# ESM-4G-V1_1.net
KiCad netlist of a schematic drawn in Altium Designer
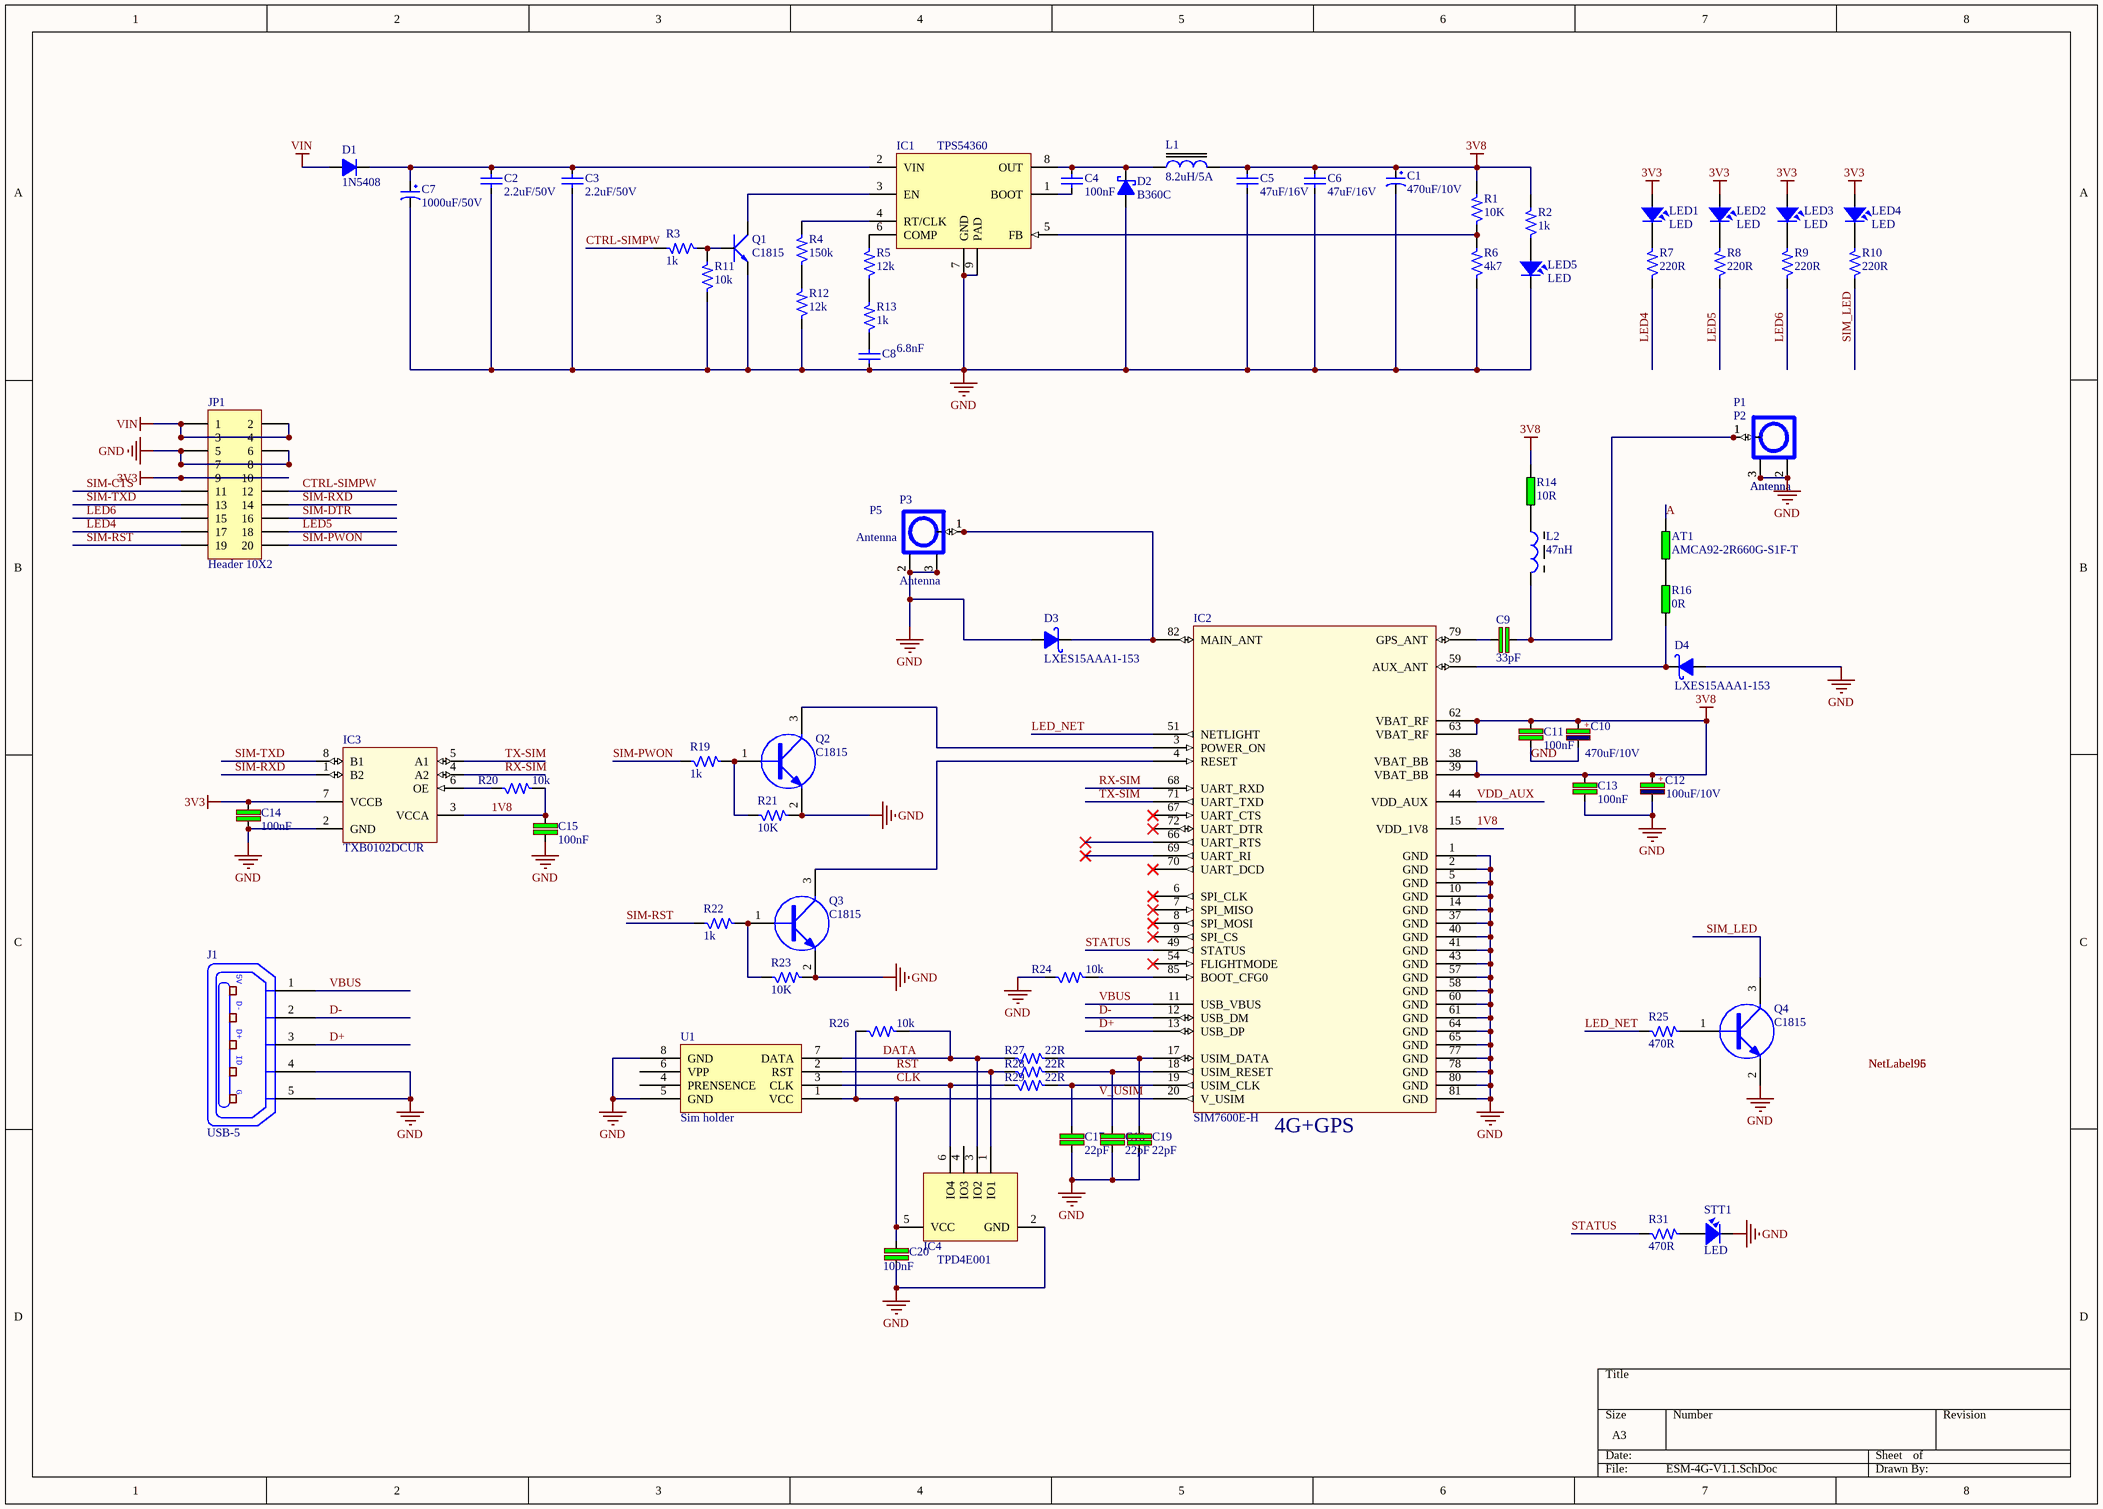
[diagram p0: ESM-4G-V1.1.SchDoc]

(export (version "E")
  (design (tool "Eeschema 10.0.6"))
  (components
    (comp (ref "AT1")
      (value "AMCA92-2R660G-S1F-T")
      (footprint "Antena-Chip - LTE")
      (description "Resistor 1/4W")
      (libsource (lib "heromap") (part "RES"))
    )
    (comp (ref "C1")
      (value "470uF/10V")
      (footprint "Anh_Trung:EEFSDE")
      (libsource (lib "Keolac") (part "CP"))
    )
    (comp (ref "C2")
      (value "2.2uF/50V")
      (footprint "Anh_Trung:C-1210")
      (description "part C3225X7R2A225K230AB")
      (libsource (lib "Keolac") (part "CN"))
    )
    (comp (ref "C3")
      (value "2.2uF/50V")
      (footprint "Anh_Trung:C-1210")
      (description "part C3225X7R2A225K230AB")
      (libsource (lib "Keolac") (part "CN"))
    )
    (comp (ref "C4") (value "100nF") (footprint "C-0805") (libsource (lib "Keolac") (part "CN")))
    (comp (ref "C5") (value "47uF/16V") (footprint "C-1210") (libsource (lib "Keolac") (part "CN")))
    (comp (ref "C6") (value "47uF/16V") (footprint "C-1210") (libsource (lib "Keolac") (part "CN")))
    (comp (ref "C7") (value "1000uF/50V") (footprint "CP5-10x16N") (libsource (lib "Keolac") (part "CP")))
    (comp (ref "C8") (value "6.8nF") (footprint "C-0805") (libsource (lib "Keolac") (part "CN")))
    (comp (ref "C9")
      (value "33pF")
      (footprint "C-0805")
      (description "Cap SMD")
      (libsource (lib "") (part "C_1"))
    )
    (comp (ref "C10")
      (value "470uF/10V")
      (footprint "EEFSDE")
      (description "Cap 1000uF/16V - 220uF/50V")
      (libsource (lib "heromap") (part "CP4"))
    )
    (comp (ref "C11")
      (value "100nF")
      (footprint "C-0805")
      (description "Cap SMD")
      (libsource (lib "heromap") (part "C"))
    )
    (comp (ref "C12")
      (value "100uF/10V")
      (footprint "EEFSDE")
      (description "Cap 1000uF/16V - 220uF/50V")
      (libsource (lib "heromap") (part "CP4"))
    )
    (comp (ref "C13")
      (value "100nF")
      (footprint "C-0805")
      (description "Cap SMD")
      (libsource (lib "heromap") (part "C"))
    )
    (comp (ref "C14")
      (value "100nF")
      (footprint "C-0805")
      (description "Cap SMD")
      (libsource (lib "heromap") (part "C"))
    )
    (comp (ref "C15")
      (value "100nF")
      (footprint "C-0805")
      (description "Cap SMD")
      (libsource (lib "heromap") (part "C"))
    )
    (comp (ref "C17")
      (value "22pF")
      (footprint "C-0805")
      (description "Cap SMD")
      (libsource (lib "heromap") (part "C"))
    )
    (comp (ref "C18")
      (value "22pF")
      (footprint "C-0805")
      (description "Cap SMD")
      (libsource (lib "heromap") (part "C"))
    )
    (comp (ref "C19")
      (value "22pF")
      (footprint "C-0805")
      (description "Cap SMD")
      (libsource (lib "heromap") (part "C"))
    )
    (comp (ref "C20")
      (value "100nF")
      (footprint "C-0805")
      (description "Cap SMD")
      (libsource (lib "heromap") (part "C"))
    )
    (comp (ref "D1")
      (value "1N5408")
      (footprint "Duy_Hai:SMB")
      (description "Diode S3M 3A 1000V")
      (libsource (lib "Keolac") (part "Diode"))
    )
    (comp (ref "D2")
      (value "B360C")
      (footprint "DUNV:SMB")
      (description "part: B560C-13-F")
      (libsource (lib "Keolac") (part "Diode scotky"))
    )
    (comp (ref "D3")
      (value "LXES15AAA1-153")
      (footprint "R-0402")
      (libsource (lib "Anh_Trung") (part "1N5822"))
    )
    (comp (ref "D4")
      (value "LXES15AAA1-153")
      (footprint "R-0402")
      (libsource (lib "Anh_Trung") (part "1N5822"))
    )
    (comp (ref "IC1")
      (value "TPS54360")
      (footprint "Anh_Trung:SOIC-8 - PW")
      (description "TPS54360 60 V Input, 3.5 A, Step Down DC-DC Converter with Eco-mode™")
      (libsource (lib "Keolac") (part "TPS54360"))
    )
    (comp (ref "IC2")
      (value "SIM7600E-H")
      (footprint "SIM7600")
      (description "SIM7600E-H GSM/LTE CAT4/GPS")
      (libsource (lib "Anh_Trung") (part "SIM7600E-H"))
    )
    (comp (ref "IC3")
      (value "TXB0102DCUR")
      (footprint "Duy_Hai:US8")
      (description "2-BIT BIDIRECTIONAL VOLTAGE-LEVEL TRANSLATOR")
      (libsource (lib "Anh_Trung") (part "TXB0102DCUR"))
    )
    (comp (ref "IC4")
      (value "TPD4E001")
      (footprint "SOT23-6 - 2")
      (libsource (lib "heromap") (part "TPD4E001"))
    )
    (comp (ref "J1")
      (value "USB-5")
      (footprint "USB-M2")
      (fields
        (field (name "MANUFACTURER") "FCI")
        (field (name "MANUFACTURER PART NUMBER") "10118193-0001LF")
        (field (name ".CREATOR") "MM")
        (field (name ".CHECKED PCB") "RF")
        (field (name ".CHECKED SCH") "MM")
      )
      (libsource (lib "Duy_Hai") (part "USB-5"))
    )
    (comp (ref "JP1")
      (value "Header 10X2")
      (footprint "Duy_Hai:JP10x2-FMD-2.54")
      (description "Header, 10-Pin, Dual row")
      (fields (field (name "PUBLISHER") "Altium Limited"))
      (libsource (lib "heromap") (part "Header 10X2"))
    )
    (comp (ref "L1")
      (value "8.2uH/5A")
      (footprint "Keolac:L-L-12x12")
      (description "part: 7447797820")
      (libsource (lib "Keolac") (part "L1"))
    )
    (comp (ref "L2")
      (value "47nH")
      (footprint "L-0805")
      (description "Ferrite Beads Rated current > 1A")
      (libsource (lib "heromap") (part "Inductor Ferit"))
    )
    (comp (ref "LED1") (value "LED") (footprint "Keolac:LED-5-N") (libsource (lib "Keolac") (part "LED")))
    (comp (ref "LED2") (value "LED") (footprint "Keolac:LED-5-N") (libsource (lib "Keolac") (part "LED")))
    (comp (ref "LED3") (value "LED") (footprint "Keolac:LED-5-N") (libsource (lib "Keolac") (part "LED")))
    (comp (ref "LED4") (value "LED") (footprint "Keolac:LED-5-N") (libsource (lib "Keolac") (part "LED")))
    (comp (ref "LED5") (value "LED") (footprint "Anh_Trung:LED-0805") (libsource (lib "Keolac") (part "LED")))
    (comp (ref "P1")
      (value "Antenna")
      (footprint "Duy_Hai:IPXS_1")
      (description "Antenna GSM GPS")
      (libsource (lib "heromap") (part "IPXSx66"))
    )
    (comp (ref "P2")
      (value "Antenna")
      (footprint "IPXS")
      (description "Antenna GSM GPS")
      (libsource (lib "heromap") (part "IPXSx66"))
    )
    (comp (ref "P3")
      (value "Antenna")
      (footprint "Duy_Hai:IPXS_1")
      (description "Antenna GSM GPS")
      (libsource (lib "") (part "IPXSx66_1"))
    )
    (comp (ref "P5")
      (value "Antenna")
      (footprint "IPXS")
      (description "Antenna GSM GPS")
      (libsource (lib "") (part "IPXSx66_1"))
    )
    (comp (ref "Q1")
      (value "C1815")
      (footprint "Keolac:SOT23-3 Tran")
      (libsource (lib "Keolac") (part "C1815"))
    )
    (comp (ref "Q2")
      (value "C1815")
      (footprint "SOT23")
      (description "Transistor C1815, SOT23")
      (fields (field (name "NAME") "C1815"))
      (libsource (lib "Library") (part "NPN"))
    )
    (comp (ref "Q3")
      (value "C1815")
      (footprint "SOT23")
      (description "Transistor C1815, SOT23")
      (fields (field (name "NAME") "C1815"))
      (libsource (lib "Library") (part "NPN"))
    )
    (comp (ref "Q4")
      (value "C1815(MMBT4401)")
      (footprint "SOT23")
      (description "Transistor C1815, SOT23")
      (fields (field (name "NAME") "C1815"))
      (libsource (lib "Library") (part "NPN"))
    )
    (comp (ref "R1")
      (value "10K")
      (footprint "Anh_Trung:R-0805")
      (description "Resistor 1/4W")
      (libsource (lib "Keolac") (part "R"))
    )
    (comp (ref "R2")
      (value "1k")
      (footprint "Anh_Trung:R-0805")
      (description "Resistor 1/4W")
      (libsource (lib "Keolac") (part "R"))
    )
    (comp (ref "R3")
      (value "1k")
      (footprint "Anh_Trung:R-0805")
      (description "Resistor 1/4W")
      (libsource (lib "Keolac") (part "R"))
    )
    (comp (ref "R4")
      (value "150k")
      (footprint "Anh_Trung:R-0805")
      (description "Resistor 1/4W")
      (libsource (lib "Keolac") (part "R"))
    )
    (comp (ref "R5")
      (value "12k")
      (footprint "R-0805")
      (description "Resistor 1/4W")
      (libsource (lib "Keolac") (part "R"))
    )
    (comp (ref "R6")
      (value "4k7")
      (footprint "Anh_Trung:R-0805")
      (description "Resistor 1/4W")
      (libsource (lib "Keolac") (part "R"))
    )
    (comp (ref "R7")
      (value "220R")
      (footprint "Anh_Trung:R-0805")
      (description "Resistor 1/4W")
      (libsource (lib "Keolac") (part "R"))
    )
    (comp (ref "R8")
      (value "220R")
      (footprint "Anh_Trung:R-0805")
      (description "Resistor 1/4W")
      (libsource (lib "Keolac") (part "R"))
    )
    (comp (ref "R9")
      (value "220R")
      (footprint "Anh_Trung:R-0805")
      (description "Resistor 1/4W")
      (libsource (lib "Keolac") (part "R"))
    )
    (comp (ref "R10")
      (value "220R")
      (footprint "Anh_Trung:R-0805")
      (description "Resistor 1/4W")
      (libsource (lib "Keolac") (part "R"))
    )
    (comp (ref "R11")
      (value "10k")
      (footprint "Anh_Trung:R-0805")
      (description "Resistor 1/4W")
      (libsource (lib "Keolac") (part "R"))
    )
    (comp (ref "R12")
      (value "12k")
      (footprint "Anh_Trung:R-0805")
      (description "Resistor 1/4W")
      (libsource (lib "Keolac") (part "R"))
    )
    (comp (ref "R13")
      (value "1k")
      (footprint "Anh_Trung:R-0805")
      (description "Resistor 1/4W")
      (libsource (lib "Keolac") (part "R"))
    )
    (comp (ref "R14")
      (value "10R")
      (footprint "R-0805")
      (description "Resistor 1/4W")
      (libsource (lib "heromap") (part "RES"))
    )
    (comp (ref "R16")
      (value "0R")
      (footprint "R-0805")
      (description "Resistor 1/4W")
      (libsource (lib "heromap") (part "RES"))
    )
    (comp (ref "R19")
      (value "1k")
      (footprint "R-0805")
      (description "Resistor 1/4W")
      (libsource (lib "Keolac") (part "R"))
    )
    (comp (ref "R20")
      (value "10k")
      (footprint "R-0805")
      (description "Resistor 1/4W")
      (libsource (lib "Keolac") (part "R"))
    )
    (comp (ref "R21")
      (value "10K")
      (footprint "R-0805")
      (description "Resistor 1/4W")
      (libsource (lib "Keolac") (part "R"))
    )
    (comp (ref "R22")
      (value "1k")
      (footprint "R-0805")
      (description "Resistor 1/4W")
      (libsource (lib "Keolac") (part "R"))
    )
    (comp (ref "R23")
      (value "10K")
      (footprint "R-0805")
      (description "Resistor 1/4W")
      (libsource (lib "Keolac") (part "R"))
    )
    (comp (ref "R24")
      (value "10k")
      (footprint "R-0805")
      (description "Resistor 1/4W")
      (libsource (lib "Keolac") (part "R"))
    )
    (comp (ref "R25")
      (value "470R")
      (footprint "R-0805")
      (description "Resistor 1/4W")
      (libsource (lib "heromap") (part "R"))
    )
    (comp (ref "R26")
      (value "10k")
      (footprint "R-0805")
      (description "Resistor 1/4W")
      (libsource (lib "Keolac") (part "R"))
    )
    (comp (ref "R27")
      (value "22R")
      (footprint "R-0805")
      (description "Resistor 1/4W")
      (libsource (lib "Keolac") (part "R"))
    )
    (comp (ref "R28")
      (value "22R")
      (footprint "R-0805")
      (description "Resistor 1/4W")
      (libsource (lib "Keolac") (part "R"))
    )
    (comp (ref "R29")
      (value "22R")
      (footprint "R-0805")
      (description "Resistor 1/4W")
      (libsource (lib "Keolac") (part "R"))
    )
    (comp (ref "R31")
      (value "470R")
      (footprint "R-0805")
      (description "Resistor 1/4W")
      (libsource (lib "heromap") (part "R"))
    )
    (comp (ref "STT1")
      (value "LED")
      (footprint "LED-SMD-0805")
      (description "LED Single colour Green and Red")
      (libsource (lib "heromap") (part "LED"))
    )
    (comp (ref "U1")
      (value "Sim holder")
      (footprint "Duy_Hai:SIM_HOLDER")
      (libsource (lib "Sim holder") (part "Component_1"))
    )
  )
  (nets
    (net (code "1") (name "/1V8") (class "Default")
      (node (ref "C15") (pin "1") (pinfunction "1_1") (pintype "passive"))
      (node (ref "IC2") (pin "15") (pinfunction "VDD_1V8_15") (pintype "passive"))
      (node (ref "IC3") (pin "3") (pinfunction "VCCA_3") (pintype "power_in"))
      (node (ref "R20") (pin "2") (pinfunction "2_2") (pintype "passive"))
    )
    (net (code "2") (name "/A") (class "Default")
      (node (ref "AT1") (pin "2") (pinfunction "2_2") (pintype "passive"))
    )
    (net (code "3") (name "/CLK") (class "Default")
      (node (ref "IC4") (pin "6") (pinfunction "IO4_6") (pintype "passive"))
      (node (ref "R29") (pin "1") (pinfunction "1_1") (pintype "passive"))
      (node (ref "U1") (pin "3") (pinfunction "CLK_3") (pintype "passive"))
    )
    (net (code "4") (name "/CTRL-SIMPW") (class "Default")
      (node (ref "JP1") (pin "12") (pinfunction "12_12") (pintype "passive"))
      (node (ref "R3") (pin "2") (pinfunction "2_2") (pintype "passive"))
    )
    (net (code "5") (name "/D+") (class "Default")
      (node (ref "IC2") (pin "13") (pinfunction "USB_DP_13") (pintype "bidirectional"))
      (node (ref "J1") (pin "3") (pinfunction "P3_3") (pintype "passive"))
    )
    (net (code "6") (name "/D-") (class "Default")
      (node (ref "IC2") (pin "12") (pinfunction "USB_DM_12") (pintype "bidirectional"))
      (node (ref "J1") (pin "2") (pinfunction "P2_2") (pintype "passive"))
    )
    (net (code "7") (name "/DATA") (class "Default")
      (node (ref "IC4") (pin "3") (pinfunction "IO2_3") (pintype "passive"))
      (node (ref "R26") (pin "2") (pinfunction "2_2") (pintype "passive"))
      (node (ref "R27") (pin "1") (pinfunction "1_1") (pintype "passive"))
      (node (ref "U1") (pin "7") (pinfunction "DATA_7") (pintype "passive"))
    )
    (net (code "8") (name "/LED4") (class "Default")
      (node (ref "JP1") (pin "17") (pinfunction "17_17") (pintype "passive"))
      (node (ref "R7") (pin "1") (pinfunction "1_1") (pintype "passive"))
    )
    (net (code "9") (name "/LED5") (class "Default")
      (node (ref "JP1") (pin "18") (pinfunction "18_18") (pintype "passive"))
      (node (ref "R8") (pin "1") (pinfunction "1_1") (pintype "passive"))
    )
    (net (code "10") (name "/LED6") (class "Default")
      (node (ref "JP1") (pin "15") (pinfunction "15_15") (pintype "passive"))
      (node (ref "R9") (pin "1") (pinfunction "1_1") (pintype "passive"))
    )
    (net (code "11") (name "/LED_NET") (class "Default")
      (node (ref "IC2") (pin "51") (pinfunction "NETLIGHT_51") (pintype "output"))
      (node (ref "R25") (pin "1") (pinfunction "1_1") (pintype "passive"))
    )
    (net (code "13") (name "/RST") (class "Default")
      (node (ref "IC4") (pin "1") (pinfunction "IO1_1") (pintype "passive"))
      (node (ref "R28") (pin "1") (pinfunction "1_1") (pintype "passive"))
      (node (ref "U1") (pin "2") (pinfunction "RST_2") (pintype "passive"))
    )
    (net (code "14") (name "/RX-SIM") (class "Default")
      (node (ref "IC2") (pin "68") (pinfunction "UART_RXD_68") (pintype "input"))
      (node (ref "IC3") (pin "4") (pinfunction "A2_4") (pintype "bidirectional"))
    )
    (net (code "15") (name "/SIM-CTS") (class "Default")
      (node (ref "JP1") (pin "11") (pinfunction "11_11") (pintype "passive"))
    )
    (net (code "16") (name "/SIM-DTR") (class "Default")
      (node (ref "JP1") (pin "16") (pinfunction "16_16") (pintype "passive"))
    )
    (net (code "17") (name "/SIM-PWON") (class "Default")
      (node (ref "JP1") (pin "20") (pinfunction "20_20") (pintype "passive"))
      (node (ref "R19") (pin "1") (pinfunction "1_1") (pintype "passive"))
    )
    (net (code "18") (name "/SIM-RST") (class "Default")
      (node (ref "JP1") (pin "19") (pinfunction "19_19") (pintype "passive"))
      (node (ref "R22") (pin "1") (pinfunction "1_1") (pintype "passive"))
    )
    (net (code "19") (name "/SIM-RXD") (class "Default")
      (node (ref "IC3") (pin "1") (pinfunction "B2_1") (pintype "bidirectional"))
      (node (ref "JP1") (pin "14") (pinfunction "14_14") (pintype "passive"))
    )
    (net (code "20") (name "/SIM-TXD") (class "Default")
      (node (ref "IC3") (pin "8") (pinfunction "B1_8") (pintype "bidirectional"))
      (node (ref "JP1") (pin "13") (pinfunction "13_13") (pintype "passive"))
    )
    (net (code "21") (name "/SIM_LED") (class "Default")
      (node (ref "Q4") (pin "3") (pinfunction "C_3") (pintype "passive"))
      (node (ref "R10") (pin "1") (pinfunction "1_1") (pintype "passive"))
    )
    (net (code "22") (name "/STATUS") (class "Default")
      (node (ref "IC2") (pin "49") (pinfunction "STATUS_49") (pintype "output"))
      (node (ref "R31") (pin "1") (pinfunction "1_1") (pintype "passive"))
    )
    (net (code "23") (name "/TX-SIM") (class "Default")
      (node (ref "IC2") (pin "71") (pinfunction "UART_TXD_71") (pintype "output"))
      (node (ref "IC3") (pin "5") (pinfunction "A1_5") (pintype "bidirectional"))
    )
    (net (code "24") (name "/VBUS") (class "Default")
      (node (ref "IC2") (pin "11") (pinfunction "USB_VBUS_11") (pintype "passive"))
      (node (ref "J1") (pin "1") (pinfunction "P1_1") (pintype "passive"))
    )
    (net (code "25") (name "/VDD_AUX") (class "Default")
      (node (ref "IC2") (pin "44") (pinfunction "VDD_AUX_44") (pintype "passive"))
    )
    (net (code "26") (name "/V_USIM") (class "Default")
      (node (ref "C20") (pin "1") (pinfunction "1_1") (pintype "passive"))
      (node (ref "IC2") (pin "20") (pinfunction "V_USIM_20") (pintype "output"))
      (node (ref "IC4") (pin "5") (pinfunction "VCC_5") (pintype "passive"))
      (node (ref "R26") (pin "1") (pinfunction "1_1") (pintype "passive"))
      (node (ref "U1") (pin "1") (pinfunction "VCC_1") (pintype "passive"))
    )
    (net (code "27") (name "3V3") (class "Default")
      (node (ref "C14") (pin "1") (pinfunction "1_1") (pintype "passive"))
      (node (ref "IC3") (pin "7") (pinfunction "VCCB_7") (pintype "power_in"))
      (node (ref "JP1") (pin "10") (pinfunction "10_10") (pintype "passive"))
      (node (ref "JP1") (pin "9") (pinfunction "9_9") (pintype "passive"))
      (node (ref "LED1") (pin "1") (pinfunction "1_1") (pintype "passive"))
      (node (ref "LED2") (pin "1") (pinfunction "1_1") (pintype "passive"))
      (node (ref "LED3") (pin "1") (pinfunction "1_1") (pintype "passive"))
      (node (ref "LED4") (pin "1") (pinfunction "1_1") (pintype "passive"))
    )
    (net (code "28") (name "3V8") (class "Default")
      (node (ref "C1") (pin "1") (pinfunction "1_1") (pintype "passive"))
      (node (ref "C10") (pin "1") (pinfunction "1_1") (pintype "passive"))
      (node (ref "C11") (pin "1") (pinfunction "1_1") (pintype "passive"))
      (node (ref "C12") (pin "1") (pinfunction "1_1") (pintype "passive"))
      (node (ref "C13") (pin "1") (pinfunction "1_1") (pintype "passive"))
      (node (ref "C5") (pin "2") (pinfunction "2_2") (pintype "passive"))
      (node (ref "C6") (pin "2") (pinfunction "2_2") (pintype "passive"))
      (node (ref "IC2") (pin "38") (pinfunction "VBAT_BB_38") (pintype "passive"))
      (node (ref "IC2") (pin "39") (pinfunction "VBAT_BB_39") (pintype "passive"))
      (node (ref "IC2") (pin "62") (pinfunction "VBAT_RF_62") (pintype "passive"))
      (node (ref "IC2") (pin "63") (pinfunction "VBAT_RF_63") (pintype "passive"))
      (node (ref "L1") (pin "2") (pinfunction "2_2") (pintype "passive"))
      (node (ref "R1") (pin "2") (pinfunction "2_2") (pintype "passive"))
      (node (ref "R14") (pin "2") (pinfunction "2_2") (pintype "passive"))
      (node (ref "R2") (pin "2") (pinfunction "2_2") (pintype "passive"))
    )
    (net (code "29") (name "GND") (class "Default")
      (node (ref "C1") (pin "2") (pinfunction "2_2") (pintype "passive"))
      (node (ref "C10") (pin "2") (pinfunction "2_2") (pintype "passive"))
      (node (ref "C11") (pin "2") (pinfunction "2_2") (pintype "passive"))
      (node (ref "C12") (pin "2") (pinfunction "2_2") (pintype "passive"))
      (node (ref "C13") (pin "2") (pinfunction "2_2") (pintype "passive"))
      (node (ref "C14") (pin "2") (pinfunction "2_2") (pintype "passive"))
      (node (ref "C15") (pin "2") (pinfunction "2_2") (pintype "passive"))
      (node (ref "C17") (pin "2") (pinfunction "2_2") (pintype "passive"))
      (node (ref "C18") (pin "2") (pinfunction "2_2") (pintype "passive"))
      (node (ref "C19") (pin "2") (pinfunction "2_2") (pintype "passive"))
      (node (ref "C2") (pin "1") (pinfunction "1_1") (pintype "passive"))
      (node (ref "C20") (pin "2") (pinfunction "2_2") (pintype "passive"))
      (node (ref "C3") (pin "1") (pinfunction "1_1") (pintype "passive"))
      (node (ref "C5") (pin "1") (pinfunction "1_1") (pintype "passive"))
      (node (ref "C6") (pin "1") (pinfunction "1_1") (pintype "passive"))
      (node (ref "C7") (pin "2") (pinfunction "2_2") (pintype "passive"))
      (node (ref "C8") (pin "1") (pinfunction "1_1") (pintype "passive"))
      (node (ref "D2") (pin "1") (pinfunction "A_1") (pintype "passive"))
      (node (ref "D3") (pin "1") (pinfunction "A_1") (pintype "passive"))
      (node (ref "D4") (pin "1") (pinfunction "A_1") (pintype "passive"))
      (node (ref "IC1") (pin "7") (pinfunction "GND_7") (pintype "power_in"))
      (node (ref "IC1") (pin "9") (pinfunction "PAD_9") (pintype "power_in"))
      (node (ref "IC2") (pin "1") (pinfunction "GND_1") (pintype "passive"))
      (node (ref "IC2") (pin "10") (pinfunction "GND_10") (pintype "passive"))
      (node (ref "IC2") (pin "14") (pinfunction "GND_14") (pintype "passive"))
      (node (ref "IC2") (pin "2") (pinfunction "GND_2") (pintype "passive"))
      (node (ref "IC2") (pin "37") (pinfunction "GND_37") (pintype "passive"))
      (node (ref "IC2") (pin "40") (pinfunction "GND_40") (pintype "passive"))
      (node (ref "IC2") (pin "41") (pinfunction "GND_41") (pintype "passive"))
      (node (ref "IC2") (pin "43") (pinfunction "GND_43") (pintype "passive"))
      (node (ref "IC2") (pin "5") (pinfunction "GND_5") (pintype "passive"))
      (node (ref "IC2") (pin "57") (pinfunction "GND_57") (pintype "passive"))
      (node (ref "IC2") (pin "58") (pinfunction "GND_58") (pintype "passive"))
      (node (ref "IC2") (pin "60") (pinfunction "GND_60") (pintype "passive"))
      (node (ref "IC2") (pin "61") (pinfunction "GND_61") (pintype "passive"))
      (node (ref "IC2") (pin "64") (pinfunction "GND_64") (pintype "passive"))
      (node (ref "IC2") (pin "65") (pinfunction "GND_65") (pintype "passive"))
      (node (ref "IC2") (pin "77") (pinfunction "GND_77") (pintype "passive"))
      (node (ref "IC2") (pin "78") (pinfunction "GND_78") (pintype "passive"))
      (node (ref "IC2") (pin "80") (pinfunction "GND_80") (pintype "passive"))
      (node (ref "IC2") (pin "81") (pinfunction "GND_81") (pintype "passive"))
      (node (ref "IC3") (pin "2") (pinfunction "GND_2") (pintype "power_in"))
      (node (ref "IC4") (pin "2") (pinfunction "GND_2") (pintype "passive"))
      (node (ref "J1") (pin "4") (pinfunction "P4_4") (pintype "passive"))
      (node (ref "J1") (pin "5") (pinfunction "P5_5") (pintype "passive"))
      (node (ref "JP1") (pin "5") (pinfunction "5_5") (pintype "passive"))
      (node (ref "JP1") (pin "6") (pinfunction "6_6") (pintype "passive"))
      (node (ref "JP1") (pin "7") (pinfunction "7_7") (pintype "passive"))
      (node (ref "JP1") (pin "8") (pinfunction "8_8") (pintype "passive"))
      (node (ref "LED5") (pin "2") (pinfunction "2_2") (pintype "passive"))
      (node (ref "P1") (pin "2") (pintype "passive"))
      (node (ref "P1") (pin "3") (pintype "passive"))
      (node (ref "P2") (pin "2") (pintype "passive"))
      (node (ref "P2") (pin "3") (pintype "passive"))
      (node (ref "P3") (pin "2") (pintype "passive"))
      (node (ref "P3") (pin "3") (pintype "passive"))
      (node (ref "P5") (pin "2") (pintype "passive"))
      (node (ref "P5") (pin "3") (pintype "passive"))
      (node (ref "Q1") (pin "1") (pinfunction "E_1") (pintype "passive"))
      (node (ref "Q2") (pin "2") (pinfunction "E_2") (pintype "passive"))
      (node (ref "Q3") (pin "2") (pinfunction "E_2") (pintype "passive"))
      (node (ref "Q4") (pin "2") (pinfunction "E_2") (pintype "passive"))
      (node (ref "R11") (pin "1") (pinfunction "1_1") (pintype "passive"))
      (node (ref "R12") (pin "1") (pinfunction "1_1") (pintype "passive"))
      (node (ref "R21") (pin "2") (pinfunction "2_2") (pintype "passive"))
      (node (ref "R23") (pin "2") (pinfunction "2_2") (pintype "passive"))
      (node (ref "R24") (pin "1") (pinfunction "1_1") (pintype "passive"))
      (node (ref "R6") (pin "1") (pinfunction "1_1") (pintype "passive"))
      (node (ref "STT1") (pin "2") (pinfunction "2_2") (pintype "passive"))
      (node (ref "U1") (pin "5") (pinfunction "GND_5") (pintype "passive"))
      (node (ref "U1") (pin "8") (pinfunction "GND_8") (pintype "passive"))
    )
    (net (code "30") (name "Net-(AT1-Pad1)") (class "Default")
      (node (ref "AT1") (pin "1") (pinfunction "1_1") (pintype "passive"))
      (node (ref "R16") (pin "2") (pinfunction "2_2") (pintype "passive"))
    )
    (net (code "31") (name "Net-(C8-Pad2)") (class "Default")
      (node (ref "C8") (pin "2") (pinfunction "2_2") (pintype "passive"))
      (node (ref "R13") (pin "1") (pinfunction "1_1") (pintype "passive"))
    )
    (net (code "32") (name "Net-(C9-Pad2)") (class "Default")
      (node (ref "C9") (pin "2") (pinfunction "2_2") (pintype "passive"))
      (node (ref "L2") (pin "2") (pinfunction "2_2") (pintype "passive"))
      (node (ref "P1") (pin "1") (pintype "bidirectional"))
      (node (ref "P2") (pin "1") (pintype "bidirectional"))
    )
    (net (code "33") (name "Net-(D1-K)") (class "Default")
      (node (ref "C2") (pin "2") (pinfunction "2_2") (pintype "passive"))
      (node (ref "C3") (pin "2") (pinfunction "2_2") (pintype "passive"))
      (node (ref "C7") (pin "1") (pinfunction "1_1") (pintype "passive"))
      (node (ref "D1") (pin "2") (pinfunction "K_2") (pintype "passive"))
      (node (ref "IC1") (pin "2") (pinfunction "VIN_2") (pintype "power_in"))
    )
    (net (code "34") (name "Net-(D2-K)") (class "Default")
      (node (ref "C4") (pin "2") (pinfunction "2_2") (pintype "passive"))
      (node (ref "D2") (pin "2") (pinfunction "K_2") (pintype "passive"))
      (node (ref "IC1") (pin "8") (pinfunction "OUT_8") (pintype "power_in"))
      (node (ref "L1") (pin "1") (pinfunction "1_1") (pintype "passive"))
    )
    (net (code "35") (name "Net-(D3-K)") (class "Default")
      (node (ref "D3") (pin "2") (pinfunction "K_2") (pintype "passive"))
      (node (ref "IC2") (pin "82") (pinfunction "MAIN_ANT_82") (pintype "bidirectional"))
      (node (ref "P3") (pin "1") (pintype "bidirectional"))
      (node (ref "P5") (pin "1") (pintype "bidirectional"))
    )
    (net (code "36") (name "Net-(D4-K)") (class "Default")
      (node (ref "D4") (pin "2") (pinfunction "K_2") (pintype "passive"))
      (node (ref "IC2") (pin "59") (pinfunction "AUX_ANT_59") (pintype "bidirectional"))
      (node (ref "R16") (pin "1") (pinfunction "1_1") (pintype "passive"))
    )
    (net (code "37") (name "Net-(IC1-BOOT)") (class "Default")
      (node (ref "C4") (pin "1") (pinfunction "1_1") (pintype "passive"))
      (node (ref "IC1") (pin "1") (pinfunction "BOOT_1") (pintype "power_in"))
    )
    (net (code "38") (name "Net-(IC1-COMP)") (class "Default")
      (node (ref "IC1") (pin "6") (pinfunction "COMP_6") (pintype "power_in"))
      (node (ref "R5") (pin "2") (pinfunction "2_2") (pintype "passive"))
    )
    (net (code "39") (name "Net-(IC1-EN)") (class "Default")
      (node (ref "IC1") (pin "3") (pinfunction "EN_3") (pintype "open_collector"))
      (node (ref "Q1") (pin "2") (pinfunction "C_2") (pintype "passive"))
    )
    (net (code "40") (name "Net-(IC1-FB)") (class "Default")
      (node (ref "IC1") (pin "5") (pinfunction "FB_5") (pintype "input"))
      (node (ref "R1") (pin "1") (pinfunction "1_1") (pintype "passive"))
      (node (ref "R6") (pin "2") (pinfunction "2_2") (pintype "passive"))
    )
    (net (code "41") (name "Net-(IC1-RT{slash}CLK)") (class "Default")
      (node (ref "IC1") (pin "4") (pinfunction "RT/CLK_4") (pintype "power_in"))
      (node (ref "R4") (pin "2") (pinfunction "2_2") (pintype "passive"))
    )
    (net (code "42") (name "Net-(IC2-BOOT_CFG0)") (class "Default")
      (node (ref "IC2") (pin "85") (pinfunction "BOOT_CFG0_85") (pintype "input"))
      (node (ref "R24") (pin "2") (pinfunction "2_2") (pintype "passive"))
    )
    (net (code "43") (name "Net-(IC2-GPS_ANT)") (class "Default")
      (node (ref "C9") (pin "1") (pinfunction "1_1") (pintype "passive"))
      (node (ref "IC2") (pin "79") (pinfunction "GPS_ANT_79") (pintype "bidirectional"))
    )
    (net (code "44") (name "Net-(IC2-POWER_ON)") (class "Default")
      (node (ref "IC2") (pin "3") (pinfunction "POWER_ON_3") (pintype "input"))
      (node (ref "Q2") (pin "3") (pinfunction "C_3") (pintype "passive"))
    )
    (net (code "45") (name "Net-(IC2-RESET)") (class "Default")
      (node (ref "IC2") (pin "4") (pinfunction "RESET_4") (pintype "input"))
      (node (ref "Q3") (pin "3") (pinfunction "C_3") (pintype "passive"))
    )
    (net (code "46") (name "Net-(IC2-USIM_CLK)") (class "Default")
      (node (ref "C17") (pin "1") (pinfunction "1_1") (pintype "passive"))
      (node (ref "IC2") (pin "19") (pinfunction "USIM_CLK_19") (pintype "output"))
      (node (ref "R29") (pin "2") (pinfunction "2_2") (pintype "passive"))
    )
    (net (code "47") (name "Net-(IC2-USIM_DATA)") (class "Default")
      (node (ref "C19") (pin "1") (pinfunction "1_1") (pintype "passive"))
      (node (ref "IC2") (pin "17") (pinfunction "USIM_DATA_17") (pintype "bidirectional"))
      (node (ref "R27") (pin "2") (pinfunction "2_2") (pintype "passive"))
    )
    (net (code "48") (name "Net-(IC2-USIM_RESET)") (class "Default")
      (node (ref "C18") (pin "1") (pinfunction "1_1") (pintype "passive"))
      (node (ref "IC2") (pin "18") (pinfunction "USIM_RESET_18") (pintype "output"))
      (node (ref "R28") (pin "2") (pinfunction "2_2") (pintype "passive"))
    )
    (net (code "49") (name "Net-(IC3-OE)") (class "Default")
      (node (ref "IC3") (pin "6") (pinfunction "OE_6") (pintype "input"))
      (node (ref "R20") (pin "1") (pinfunction "1_1") (pintype "passive"))
    )
    (net (code "50") (name "Net-(L2-Pad1)") (class "Default")
      (node (ref "L2") (pin "1") (pinfunction "1_1") (pintype "passive"))
      (node (ref "R14") (pin "1") (pinfunction "1_1") (pintype "passive"))
    )
    (net (code "51") (name "Net-(LED1-Pad2)") (class "Default")
      (node (ref "LED1") (pin "2") (pinfunction "2_2") (pintype "passive"))
      (node (ref "R7") (pin "2") (pinfunction "2_2") (pintype "passive"))
    )
    (net (code "52") (name "Net-(LED2-Pad2)") (class "Default")
      (node (ref "LED2") (pin "2") (pinfunction "2_2") (pintype "passive"))
      (node (ref "R8") (pin "2") (pinfunction "2_2") (pintype "passive"))
    )
    (net (code "53") (name "Net-(LED3-Pad2)") (class "Default")
      (node (ref "LED3") (pin "2") (pinfunction "2_2") (pintype "passive"))
      (node (ref "R9") (pin "2") (pinfunction "2_2") (pintype "passive"))
    )
    (net (code "54") (name "Net-(LED4-Pad2)") (class "Default")
      (node (ref "LED4") (pin "2") (pinfunction "2_2") (pintype "passive"))
      (node (ref "R10") (pin "2") (pinfunction "2_2") (pintype "passive"))
    )
    (net (code "55") (name "Net-(LED5-Pad1)") (class "Default")
      (node (ref "LED5") (pin "1") (pinfunction "1_1") (pintype "passive"))
      (node (ref "R2") (pin "1") (pinfunction "1_1") (pintype "passive"))
    )
    (net (code "56") (name "Net-(Q1-B)") (class "Default")
      (node (ref "Q1") (pin "3") (pinfunction "B_3") (pintype "passive"))
      (node (ref "R11") (pin "2") (pinfunction "2_2") (pintype "passive"))
      (node (ref "R3") (pin "1") (pinfunction "1_1") (pintype "passive"))
    )
    (net (code "57") (name "Net-(Q2-B)") (class "Default")
      (node (ref "Q2") (pin "1") (pinfunction "B_1") (pintype "passive"))
      (node (ref "R19") (pin "2") (pinfunction "2_2") (pintype "passive"))
      (node (ref "R21") (pin "1") (pinfunction "1_1") (pintype "passive"))
    )
    (net (code "58") (name "Net-(Q3-B)") (class "Default")
      (node (ref "Q3") (pin "1") (pinfunction "B_1") (pintype "passive"))
      (node (ref "R22") (pin "2") (pinfunction "2_2") (pintype "passive"))
      (node (ref "R23") (pin "1") (pinfunction "1_1") (pintype "passive"))
    )
    (net (code "59") (name "Net-(Q4-B)") (class "Default")
      (node (ref "Q4") (pin "1") (pinfunction "B_1") (pintype "passive"))
      (node (ref "R25") (pin "2") (pinfunction "2_2") (pintype "passive"))
    )
    (net (code "60") (name "Net-(R12-Pad2)") (class "Default")
      (node (ref "R12") (pin "2") (pinfunction "2_2") (pintype "passive"))
      (node (ref "R4") (pin "1") (pinfunction "1_1") (pintype "passive"))
    )
    (net (code "61") (name "Net-(R13-Pad2)") (class "Default")
      (node (ref "R13") (pin "2") (pinfunction "2_2") (pintype "passive"))
      (node (ref "R5") (pin "1") (pinfunction "1_1") (pintype "passive"))
    )
    (net (code "62") (name "Net-(R31-Pad2)") (class "Default")
      (node (ref "R31") (pin "2") (pinfunction "2_2") (pintype "passive"))
      (node (ref "STT1") (pin "1") (pinfunction "1_1") (pintype "passive"))
    )
    (net (code "63") (name "VIN") (class "Default")
      (node (ref "D1") (pin "1") (pinfunction "A_1") (pintype "passive"))
      (node (ref "JP1") (pin "1") (pinfunction "1_1") (pintype "passive"))
      (node (ref "JP1") (pin "2") (pinfunction "2_2") (pintype "passive"))
      (node (ref "JP1") (pin "3") (pinfunction "3_3") (pintype "passive"))
      (node (ref "JP1") (pin "4") (pinfunction "4_4") (pintype "passive"))
    )
    (net (code "64") (name "unconnected-(IC2-ADC1-Pad47)") (class "Default")
      (node (ref "IC2") (pin "47") (pinfunction "ADC1_47") (pintype "passive"))
    )
    (net (code "65") (name "unconnected-(IC2-ADC2-Pad46)") (class "Default")
      (node (ref "IC2") (pin "46") (pinfunction "ADC2_46") (pintype "passive"))
    )
    (net (code "66") (name "unconnected-(IC2-EAR1N-Pad25)") (class "Default")
      (node (ref "IC2") (pin "25") (pinfunction "EAR1N_25") (pintype "passive"))
    )
    (net (code "67") (name "unconnected-(IC2-EAR1P-Pad26)") (class "Default")
      (node (ref "IC2") (pin "26") (pinfunction "EAR1P_26") (pintype "passive"))
    )
    (net (code "68") (name "unconnected-(IC2-FLIGHTMODE-Pad54)") (class "Default")
      (node (ref "IC2") (pin "54") (pinfunction "FLIGHTMODE_54") (pintype "input+no_connect"))
    )
    (net (code "69") (name "unconnected-(IC2-GPIO1-Pad51)") (class "Default")
      (node (ref "IC2") (pin "51") (pinfunction "GPIO1_51") (pintype "passive"))
    )
    (net (code "70") (name "unconnected-(IC2-GPIO4-Pad54)") (class "Default")
      (node (ref "IC2") (pin "54") (pinfunction "GPIO4_54") (pintype "passive"))
    )
    (net (code "71") (name "unconnected-(IC2-GPIO40-Pad49)") (class "Default")
      (node (ref "IC2") (pin "49") (pinfunction "GPIO40_49") (pintype "passive"))
    )
    (net (code "72") (name "unconnected-(IC2-GPIO41-Pad52)") (class "Default")
      (node (ref "IC2") (pin "52") (pinfunction "GPIO41_52") (pintype "passive"))
    )
    (net (code "73") (name "unconnected-(IC2-GPIO42-Pad53)") (class "Default")
      (node (ref "IC2") (pin "53") (pinfunction "GPIO42_53") (pintype "passive"))
    )
    (net (code "74") (name "unconnected-(IC2-GPIO43-Pad50)") (class "Default")
      (node (ref "IC2") (pin "50") (pinfunction "GPIO43_50") (pintype "passive"))
    )
    (net (code "75") (name "unconnected-(IC2-GPIO44-Pad48)") (class "Default")
      (node (ref "IC2") (pin "48") (pinfunction "GPIO44_48") (pintype "passive"))
    )
    (net (code "76") (name "unconnected-(IC2-KEYPAD_0-Pad29)") (class "Default")
      (node (ref "IC2") (pin "29") (pinfunction "KEYPAD_0_29") (pintype "passive"))
    )
    (net (code "77") (name "unconnected-(IC2-KEYPAD_1-Pad33)") (class "Default")
      (node (ref "IC2") (pin "33") (pinfunction "KEYPAD_1_33") (pintype "passive"))
    )
    (net (code "78") (name "unconnected-(IC2-KEYPAD_2-Pad30)") (class "Default")
      (node (ref "IC2") (pin "30") (pinfunction "KEYPAD_2_30") (pintype "passive"))
    )
    (net (code "79") (name "unconnected-(IC2-KEYPAD_3-Pad35)") (class "Default")
      (node (ref "IC2") (pin "35") (pinfunction "KEYPAD_3_35") (pintype "passive"))
    )
    (net (code "80") (name "unconnected-(IC2-KEYPAD_4-Pad34)") (class "Default")
      (node (ref "IC2") (pin "34") (pinfunction "KEYPAD_4_34") (pintype "passive"))
    )
    (net (code "81") (name "unconnected-(IC2-KEYSENSE_N0-Pad28)") (class "Default")
      (node (ref "IC2") (pin "28") (pinfunction "KEYSENSE_N0_28") (pintype "passive"))
    )
    (net (code "82") (name "unconnected-(IC2-KEYSENSE_N1-Pad27)") (class "Default")
      (node (ref "IC2") (pin "27") (pinfunction "KEYSENSE_N1_27") (pintype "passive"))
    )
    (net (code "83") (name "unconnected-(IC2-KEYSENSE_N2-Pad31)") (class "Default")
      (node (ref "IC2") (pin "31") (pinfunction "KEYSENSE_N2_31") (pintype "passive"))
    )
    (net (code "84") (name "unconnected-(IC2-KEYSENSE_N3-Pad32)") (class "Default")
      (node (ref "IC2") (pin "32") (pinfunction "KEYSENSE_N3_32") (pintype "passive"))
    )
    (net (code "85") (name "unconnected-(IC2-KEYSENSE_N4-Pad36)") (class "Default")
      (node (ref "IC2") (pin "36") (pinfunction "KEYSENSE_N4_36") (pintype "passive"))
    )
    (net (code "86") (name "unconnected-(IC2-MIC1N-Pad24)") (class "Default")
      (node (ref "IC2") (pin "24") (pinfunction "MIC1N_24") (pintype "passive"))
    )
    (net (code "87") (name "unconnected-(IC2-MIC1P-Pad23)") (class "Default")
      (node (ref "IC2") (pin "23") (pinfunction "MIC1P_23") (pintype "passive"))
    )
    (net (code "88") (name "unconnected-(IC2-PCM_CLK-Pad76)") (class "Default")
      (node (ref "IC2") (pin "76") (pinfunction "PCM_CLK_76") (pintype "passive"))
    )
    (net (code "89") (name "unconnected-(IC2-PCM_DIN-Pad74)") (class "Default")
      (node (ref "IC2") (pin "74") (pinfunction "PCM_DIN_74") (pintype "passive"))
    )
    (net (code "90") (name "unconnected-(IC2-PCM_DOUT-Pad73)") (class "Default")
      (node (ref "IC2") (pin "73") (pinfunction "PCM_DOUT_73") (pintype "passive"))
    )
    (net (code "91") (name "unconnected-(IC2-PCM_SYNC-Pad75)") (class "Default")
      (node (ref "IC2") (pin "75") (pinfunction "PCM_SYNC_75") (pintype "passive"))
    )
    (net (code "92") (name "unconnected-(IC2-RESERVED-Pad15)") (class "Default")
      (node (ref "IC2") (pin "15") (pinfunction "RESERVED_15") (pintype "passive"))
    )
    (net (code "93") (name "unconnected-(IC2-RESERVED-Pad16)") (class "Default")
      (node (ref "IC2") (pin "16") (pinfunction "RESERVED_16") (pintype "passive"))
    )
    (net (code "94") (name "unconnected-(IC2-SPI_CLK-Pad6)") (class "Default")
      (node (ref "IC2") (pin "6") (pinfunction "SPI_CLK_6") (pintype "output+no_connect"))
    )
    (net (code "95") (name "unconnected-(IC2-SPI_CS-Pad9)") (class "Default")
      (node (ref "IC2") (pin "9") (pinfunction "SPI_CS_9") (pintype "output+no_connect"))
    )
    (net (code "96") (name "unconnected-(IC2-SPI_MISO-Pad7)") (class "Default")
      (node (ref "IC2") (pin "7") (pinfunction "SPI_MISO_7") (pintype "input+no_connect"))
    )
    (net (code "97") (name "unconnected-(IC2-SPI_MOSI-Pad8)") (class "Default")
      (node (ref "IC2") (pin "8") (pinfunction "SPI_MOSI_8") (pintype "output+no_connect"))
    )
    (net (code "98") (name "unconnected-(IC2-SPK_M-Pad21)") (class "Default")
      (node (ref "IC2") (pin "21") (pinfunction "SPK_M_21") (pintype "passive"))
    )
    (net (code "99") (name "unconnected-(IC2-SPK_P-Pad22)") (class "Default")
      (node (ref "IC2") (pin "22") (pinfunction "SPK_P_22") (pintype "passive"))
    )
    (net (code "100") (name "unconnected-(IC2-UART_CTS-Pad67)") (class "Default")
      (node (ref "IC2") (pin "67") (pinfunction "UART_CTS_67") (pintype "input+no_connect"))
    )
    (net (code "101") (name "unconnected-(IC2-UART_DCD-Pad70)") (class "Default")
      (node (ref "IC2") (pin "70") (pinfunction "UART_DCD_70") (pintype "output+no_connect"))
    )
    (net (code "102") (name "unconnected-(IC2-UART_DTR-Pad72)") (class "Default")
      (node (ref "IC2") (pin "72") (pinfunction "UART_DTR_72") (pintype "bidirectional+no_connect"))
    )
    (net (code "103") (name "unconnected-(IC2-UART_RI-Pad69)") (class "Default")
      (node (ref "IC2") (pin "69") (pinfunction "UART_RI_69") (pintype "output+no_connect"))
    )
    (net (code "104") (name "unconnected-(IC2-UART_RTS-Pad66)") (class "Default")
      (node (ref "IC2") (pin "66") (pinfunction "UART_RTS_66") (pintype "output+no_connect"))
    )
    (net (code "105") (name "unconnected-(IC4-IO3-Pad4)") (class "Default")
      (node (ref "IC4") (pin "4") (pinfunction "IO3_4") (pintype "passive"))
    )
    (net (code "106") (name "unconnected-(U1-PRENSENCE-Pad4)") (class "Default")
      (node (ref "U1") (pin "4") (pinfunction "PRENSENCE_4") (pintype "passive"))
    )
    (net (code "107") (name "unconnected-(U1-VPP-Pad6)") (class "Default")
      (node (ref "U1") (pin "6") (pinfunction "VPP_6") (pintype "passive"))
    )
  )
)
